# NFC.net
KiCad netlist of a schematic drawn in Altium Designer
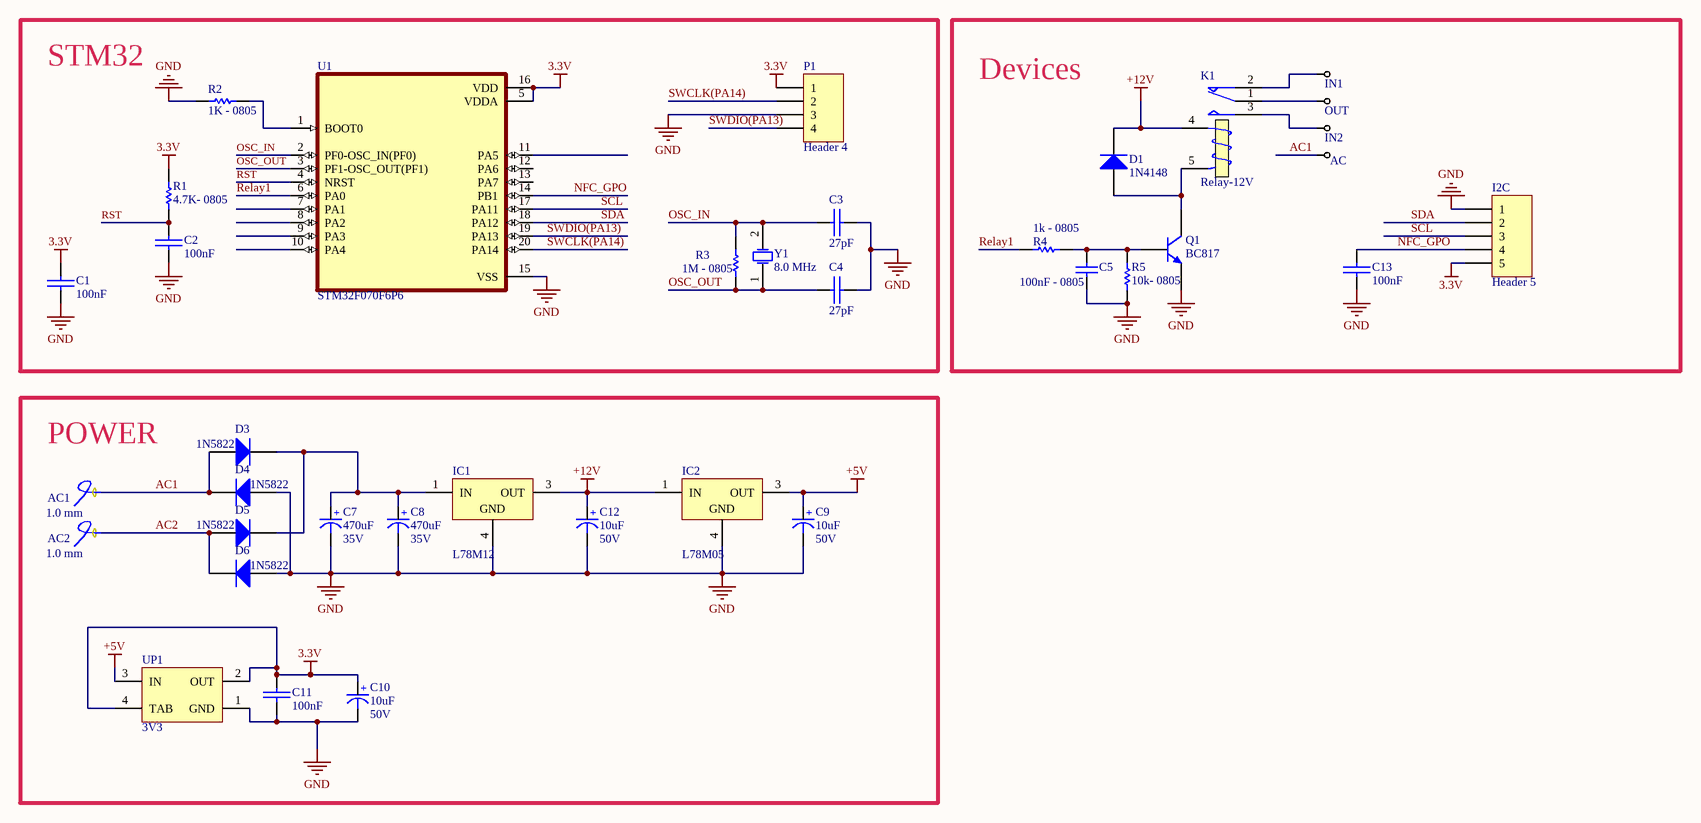
[diagram p0: NFC.SchDoc]

(export (version "E")
  (design (tool "Eeschema 10.0.6"))
  (components
    (comp (ref "AC")
      (value "Test Point")
      (footprint "Test Point")
      (libsource (lib "Altium") (part "Test Point"))
    )
    (comp (ref "AC1")
      (value "*")
      (footprint "wire 2.0 mm")
      (description "A Customize Component For Single Wire Connection")
      (fields (field (name "DIAMETER") "1.0 mm") (field (name "DESIGNER") "Saeid Jorablo"))
      (libsource (lib "My_Library") (part "Single Wire"))
    )
    (comp (ref "AC2")
      (value "*")
      (footprint "wire 2.0 mm")
      (description "A Customize Component For Single Wire Connection")
      (fields (field (name "DIAMETER") "1.0 mm") (field (name "DESIGNER") "Saeid Jorablo"))
      (libsource (lib "My_Library") (part "Single Wire"))
    )
    (comp (ref "C1")
      (value "100nF")
      (footprint "SMD_CAP_0805")
      (description "Bipolar Capacitor")
      (fields (field (name "VOLTAGE") "100V") (field (name "DESIGNER") "Saeid Jorablo"))
      (libsource (lib "My_Library") (part "Cap-Bipolar"))
    )
    (comp (ref "C2")
      (value "100nF")
      (footprint "SMD_CAP_0805")
      (description "Bipolar Capacitor")
      (fields (field (name "VOLTAGE") "100V") (field (name "DESIGNER") "Saeid Jorablo"))
      (libsource (lib "My_Library") (part "Cap-Bipolar"))
    )
    (comp (ref "C3")
      (value "27pF")
      (footprint "SMD_CAP_0805")
      (description "Bipolar Capacitor")
      (fields (field (name "VOLTAGE") "100V") (field (name "DESIGNER") "Saeid Jorablo"))
      (libsource (lib "My_Library") (part "Cap-Bipolar"))
    )
    (comp (ref "C4")
      (value "27pF")
      (footprint "SMD_CAP_0805")
      (description "Bipolar Capacitor")
      (fields (field (name "VOLTAGE") "100V") (field (name "DESIGNER") "Saeid Jorablo"))
      (libsource (lib "My_Library") (part "Cap-Bipolar"))
    )
    (comp (ref "C5")
      (value "100nF - 0805")
      (footprint "SMD_CAP_0805")
      (description "Capacitor")
      (fields (field (name "PUBLISHER") "Altium Limited"))
      (libsource (lib "Amir_Lib") (part "Cap"))
    )
    (comp (ref "C7")
      (value "470uF")
      (footprint "cap 02")
      (description "Polar Capacitor")
      (fields (field (name "VOLTAGE") "35V") (field (name "DESIGNER") "Saeid Jorablo"))
      (libsource (lib "My_Library") (part "Cap-Polar"))
    )
    (comp (ref "C8")
      (value "470uF")
      (footprint "cap 02")
      (description "Polar Capacitor")
      (fields (field (name "VOLTAGE") "35V") (field (name "DESIGNER") "Saeid Jorablo"))
      (libsource (lib "My_Library") (part "Cap-Polar"))
    )
    (comp (ref "C9")
      (value "10uF")
      (footprint "cap 01")
      (description "Polar Capacitor")
      (fields (field (name "VOLTAGE") "50V") (field (name "DESIGNER") "Saeid Jorablo"))
      (libsource (lib "My_Library") (part "Cap-Polar"))
    )
    (comp (ref "C10")
      (value "10uF")
      (footprint "cap 01")
      (description "Polar Capacitor")
      (fields (field (name "VOLTAGE") "50V") (field (name "DESIGNER") "Saeid Jorablo"))
      (libsource (lib "My_Library") (part "Cap-Polar"))
    )
    (comp (ref "C11")
      (value "100nF")
      (footprint "SMD_CAP_0805")
      (description "Bipolar Capacitor")
      (fields (field (name "VOLTAGE") "100V") (field (name "DESIGNER") "Saeid Jorablo"))
      (libsource (lib "My_Library") (part "Cap-Bipolar"))
    )
    (comp (ref "C12")
      (value "10uF")
      (footprint "cap 01")
      (description "Polar Capacitor")
      (fields (field (name "VOLTAGE") "50V") (field (name "DESIGNER") "Saeid Jorablo"))
      (libsource (lib "My_Library") (part "Cap-Polar"))
    )
    (comp (ref "C13")
      (value "100nF")
      (footprint "SMD_CAP_0805")
      (description "Bipolar Capacitor")
      (fields (field (name "VOLTAGE") "100V") (field (name "DESIGNER") "Saeid Jorablo"))
      (libsource (lib "My_Library") (part "Cap-Bipolar"))
    )
    (comp (ref "D1")
      (value "1N4148")
      (footprint "LL4148")
      (description "High Conductance Fast Diode")
      (fields (field (name "PUBLISHER") "Altium Limited"))
      (libsource (lib "My_Library") (part "Diode 1N4148"))
    )
    (comp (ref "D3")
      (value "1N5822")
      (footprint "Diode 1N4007 SMD")
      (description "High Conductance Fast Diode")
      (fields (field (name "PUBLISHER") "Altium Limited"))
      (libsource (lib "My_Library") (part "Diode 1N4148"))
    )
    (comp (ref "D4")
      (value "1N5822")
      (footprint "Diode 1N4007 SMD")
      (description "High Conductance Fast Diode")
      (fields (field (name "PUBLISHER") "Altium Limited"))
      (libsource (lib "My_Library") (part "Diode 1N4148"))
    )
    (comp (ref "D5")
      (value "1N5822")
      (footprint "Diode 1N4007 SMD")
      (description "High Conductance Fast Diode")
      (fields (field (name "PUBLISHER") "Altium Limited"))
      (libsource (lib "My_Library") (part "Diode 1N4148"))
    )
    (comp (ref "D6")
      (value "1N5822")
      (footprint "Diode 1N4007 SMD")
      (description "High Conductance Fast Diode")
      (fields (field (name "PUBLISHER") "Altium Limited"))
      (libsource (lib "My_Library") (part "Diode 1N4148"))
    )
    (comp (ref "I2C")
      (value "Header 5")
      (footprint "HDR1X5")
      (description "Header, 5-Pin")
      (fields (field (name "PUBLISHER") "Altium Limited"))
      (libsource (lib "Miscellaneous Connectors") (part "Header 5"))
    )
    (comp (ref "IC1")
      (value "L78M12")
      (footprint "TO-252")
      (description "Precision 500mA Regulator")
      (libsource (lib "My_Library") (part "L78M05"))
    )
    (comp (ref "IC2")
      (value "L78M05")
      (footprint "TO-252")
      (description "Precision 500mA Regulator")
      (libsource (lib "My_Library") (part "L78M05"))
    )
    (comp (ref "IN1")
      (value "Test Point")
      (footprint "Test Point")
      (libsource (lib "Altium") (part "Test Point"))
    )
    (comp (ref "IN2")
      (value "Test Point")
      (footprint "Test Point")
      (libsource (lib "Altium") (part "Test Point"))
    )
    (comp (ref "K1")
      (value "Relay-12V")
      (footprint "Relay 15.40x12.10x13.10")
      (description "SPDT Relay")
      (fields (field (name "DESIGNER") "Eng. Saeid Jorablo"))
      (libsource (lib "My_Library") (part "Relay"))
    )
    (comp (ref "OUT")
      (value "Test Point")
      (footprint "Test Point")
      (libsource (lib "Altium") (part "Test Point"))
    )
    (comp (ref "P1")
      (value "Header 4")
      (footprint "HDR1X4")
      (description "Header, 4-Pin")
      (fields (field (name "PUBLISHER") "Altium Limited"))
      (libsource (lib "Miscellaneous Connectors") (part "Header 4"))
    )
    (comp (ref "Q1")
      (value "BC817")
      (footprint "SOT23_N")
      (description "45 V, 500 mA NPN general-purpose transistors")
      (fields (field (name "PUBLISHER") "Abbas Basereh"))
      (libsource (lib "Altium") (part "BC817"))
    )
    (comp (ref "R1")
      (value "4.7K- 0805")
      (footprint "RES 0805 (2012X06L)")
      (description "Resistor")
      (fields (field (name "PUBLISHER") "Altium Limited"))
      (libsource (lib "Amir_Lib") (part "Res"))
    )
    (comp (ref "R2")
      (value "1K - 0805")
      (footprint "RES 0805 (2012X06L)")
      (description "Resistor")
      (fields (field (name "PUBLISHER") "Altium Limited"))
      (libsource (lib "Amir_Lib") (part "Res"))
    )
    (comp (ref "R3")
      (value "1M - 0805")
      (footprint "RES 0805 (2012X06L)")
      (description "Resistor")
      (fields (field (name "PUBLISHER") "Altium Limited"))
      (libsource (lib "Amir_Lib") (part "Res"))
    )
    (comp (ref "R4")
      (value "1k - 0805")
      (footprint "RES 0805 (2012X06L)")
      (description "Resistor")
      (fields (field (name "PUBLISHER") "Altium Limited"))
      (libsource (lib "Amir_Lib") (part "Res"))
    )
    (comp (ref "R5")
      (value "10k- 0805")
      (footprint "RES 0805 (2012X06L)")
      (description "Resistor")
      (fields (field (name "PUBLISHER") "Altium Limited"))
      (libsource (lib "Amir_Lib") (part "Res"))
    )
    (comp (ref "U1")
      (value "STM32F070F6P6")
      (footprint "SOP65P640X120-20N")
      (description "ARMÂ® CortexÂ®-M0 STM32F0 Microcontroller IC 32-Bit 48MHz 32KB _32K x 8_ FLASH 20-TSSOP")
      (fields (field (name "MF") "STMicroelectronics") (field (name "DIGI-KEY_PART_NUMBER") "497-17354-2-ND"))
      (libsource (lib "STM32F070F6P6") (part "STM32F070F6P6"))
    )
    (comp (ref "UP1")
      (value "3V3")
      (footprint "SOT223")
      (description "x.x Volt, 800mA Low-Dropout Linear Regulator, 4-pin SOT-223")
      (fields (field (name "DESIGNER") "Ali Hafizi"))
      (libsource (lib "Altium") (part "AMS1117-x.x"))
    )
    (comp (ref "Y1")
      (value "8.0 MHz")
      (footprint "Crystal SMD")
      (description "XTAL Crystal")
      (libsource (lib "My_Library") (part "XTAL"))
    )
  )
  (nets
    (net (code "1") (name "+5V") (class "Default")
      (node (ref "C9") (pin "1") (pinfunction "+_1") (pintype "passive"))
      (node (ref "IC2") (pin "3") (pinfunction "OUT_3") (pintype "power_in"))
      (node (ref "UP1") (pin "3") (pinfunction "IN_3") (pintype "power_in"))
    )
    (net (code "2") (name "+12V") (class "Default")
      (node (ref "C12") (pin "1") (pinfunction "+_1") (pintype "passive"))
      (node (ref "D1") (pin "2") (pinfunction "K_2") (pintype "passive"))
      (node (ref "IC1") (pin "3") (pinfunction "OUT_3") (pintype "power_in"))
      (node (ref "IC2") (pin "1") (pinfunction "IN_1") (pintype "power_in"))
      (node (ref "K1") (pin "4") (pinfunction "T1_4") (pintype "passive"))
    )
    (net (code "3") (name "/AC1") (class "Default")
      (node (ref "AC") (pin "1") (pinfunction "T_1") (pintype "passive"))
      (node (ref "AC1") (pin "1") (pinfunction "W_1") (pintype "passive"))
      (node (ref "D3") (pin "1") (pinfunction "A_1") (pintype "passive"))
      (node (ref "D4") (pin "2") (pinfunction "K_2") (pintype "passive"))
    )
    (net (code "4") (name "/AC2") (class "Default")
      (node (ref "AC2") (pin "1") (pinfunction "W_1") (pintype "passive"))
      (node (ref "D5") (pin "1") (pinfunction "A_1") (pintype "passive"))
      (node (ref "D6") (pin "2") (pinfunction "K_2") (pintype "passive"))
    )
    (net (code "5") (name "/NFC_GPO") (class "Default")
      (node (ref "C13") (pin "2") (pinfunction "-_2") (pintype "passive"))
      (node (ref "I2C") (pin "4") (pinfunction "4_4") (pintype "passive"))
      (node (ref "U1") (pin "14") (pinfunction "PB1_14") (pintype "bidirectional"))
    )
    (net (code "6") (name "/OSC_IN") (class "Default")
      (node (ref "C3") (pin "1") (pinfunction "+_1") (pintype "passive"))
      (node (ref "R3") (pin "2") (pinfunction "2_2") (pintype "passive"))
      (node (ref "U1") (pin "2") (pinfunction "PF0-OSC_IN(PF0)_2") (pintype "bidirectional"))
      (node (ref "Y1") (pin "2") (pinfunction "OSC2_2") (pintype "passive"))
    )
    (net (code "7") (name "/OSC_OUT") (class "Default")
      (node (ref "C4") (pin "1") (pinfunction "+_1") (pintype "passive"))
      (node (ref "R3") (pin "1") (pinfunction "1_1") (pintype "passive"))
      (node (ref "U1") (pin "3") (pinfunction "PF1-OSC_OUT(PF1)_3") (pintype "bidirectional"))
      (node (ref "Y1") (pin "1") (pinfunction "OSC1_1") (pintype "passive"))
    )
    (net (code "8") (name "/RST") (class "Default")
      (node (ref "C2") (pin "2") (pinfunction "-_2") (pintype "passive"))
      (node (ref "R1") (pin "2") (pinfunction "2_2") (pintype "passive"))
      (node (ref "U1") (pin "4") (pinfunction "NRST_4") (pintype "bidirectional"))
    )
    (net (code "9") (name "/Relay1") (class "Default")
      (node (ref "R4") (pin "2") (pinfunction "2_2") (pintype "passive"))
      (node (ref "U1") (pin "6") (pinfunction "PA0_6") (pintype "bidirectional"))
    )
    (net (code "10") (name "/SCL") (class "Default")
      (node (ref "I2C") (pin "3") (pinfunction "3_3") (pintype "passive"))
      (node (ref "U1") (pin "17") (pinfunction "PA11_17") (pintype "bidirectional"))
    )
    (net (code "11") (name "/SDA") (class "Default")
      (node (ref "I2C") (pin "2") (pinfunction "2_2") (pintype "passive"))
      (node (ref "U1") (pin "18") (pinfunction "PA12_18") (pintype "bidirectional"))
    )
    (net (code "12") (name "/SWCLK(PA14)") (class "Default")
      (node (ref "P1") (pin "2") (pinfunction "2_2") (pintype "passive"))
      (node (ref "U1") (pin "20") (pinfunction "PA14_20") (pintype "bidirectional"))
    )
    (net (code "13") (name "/SWDIO(PA13)") (class "Default")
      (node (ref "P1") (pin "4") (pinfunction "4_4") (pintype "passive"))
      (node (ref "U1") (pin "19") (pinfunction "PA13_19") (pintype "bidirectional"))
    )
    (net (code "14") (name "3.3V") (class "Default")
      (node (ref "C1") (pin "2") (pinfunction "-_2") (pintype "passive"))
      (node (ref "C10") (pin "1") (pinfunction "+_1") (pintype "passive"))
      (node (ref "C11") (pin "1") (pinfunction "+_1") (pintype "passive"))
      (node (ref "I2C") (pin "5") (pinfunction "5_5") (pintype "passive"))
      (node (ref "P1") (pin "1") (pinfunction "1_1") (pintype "passive"))
      (node (ref "R1") (pin "1") (pinfunction "1_1") (pintype "passive"))
      (node (ref "U1") (pin "16") (pinfunction "VDD_16") (pintype "power_in"))
      (node (ref "U1") (pin "5") (pinfunction "VDDA_5") (pintype "power_in"))
      (node (ref "UP1") (pin "2") (pinfunction "OUT_2") (pintype "power_in"))
      (node (ref "UP1") (pin "4") (pinfunction "TAB_4") (pintype "power_in"))
    )
    (net (code "15") (name "GND") (class "Default")
      (node (ref "C1") (pin "1") (pinfunction "+_1") (pintype "passive"))
      (node (ref "C10") (pin "2") (pinfunction "-_2") (pintype "passive"))
      (node (ref "C11") (pin "2") (pinfunction "-_2") (pintype "passive"))
      (node (ref "C12") (pin "2") (pinfunction "-_2") (pintype "passive"))
      (node (ref "C13") (pin "1") (pinfunction "+_1") (pintype "passive"))
      (node (ref "C2") (pin "1") (pinfunction "+_1") (pintype "passive"))
      (node (ref "C3") (pin "2") (pinfunction "-_2") (pintype "passive"))
      (node (ref "C4") (pin "2") (pinfunction "-_2") (pintype "passive"))
      (node (ref "C5") (pin "1") (pinfunction "1_1") (pintype "passive"))
      (node (ref "C7") (pin "2") (pinfunction "-_2") (pintype "passive"))
      (node (ref "C8") (pin "2") (pinfunction "-_2") (pintype "passive"))
      (node (ref "C9") (pin "2") (pinfunction "-_2") (pintype "passive"))
      (node (ref "D4") (pin "1") (pinfunction "A_1") (pintype "passive"))
      (node (ref "D6") (pin "1") (pinfunction "A_1") (pintype "passive"))
      (node (ref "I2C") (pin "1") (pinfunction "1_1") (pintype "passive"))
      (node (ref "IC1") (pin "4") (pinfunction "GND_4") (pintype "power_in"))
      (node (ref "IC2") (pin "4") (pinfunction "GND_4") (pintype "power_in"))
      (node (ref "P1") (pin "3") (pinfunction "3_3") (pintype "passive"))
      (node (ref "Q1") (pin "2") (pinfunction "E_2") (pintype "passive"))
      (node (ref "R2") (pin "2") (pinfunction "2_2") (pintype "passive"))
      (node (ref "R5") (pin "2") (pinfunction "2_2") (pintype "passive"))
      (node (ref "U1") (pin "15") (pinfunction "VSS_15") (pintype "power_in"))
      (node (ref "UP1") (pin "1") (pinfunction "GND_1") (pintype "power_in"))
    )
    (net (code "16") (name "Net-(C7-+)") (class "Default")
      (node (ref "C7") (pin "1") (pinfunction "+_1") (pintype "passive"))
      (node (ref "C8") (pin "1") (pinfunction "+_1") (pintype "passive"))
      (node (ref "D3") (pin "2") (pinfunction "K_2") (pintype "passive"))
      (node (ref "D5") (pin "2") (pinfunction "K_2") (pintype "passive"))
      (node (ref "IC1") (pin "1") (pinfunction "IN_1") (pintype "power_in"))
    )
    (net (code "17") (name "Net-(D1-A)") (class "Default")
      (node (ref "D1") (pin "1") (pinfunction "A_1") (pintype "passive"))
      (node (ref "K1") (pin "5") (pinfunction "T2_5") (pintype "passive"))
      (node (ref "Q1") (pin "3") (pinfunction "C_3") (pintype "passive"))
    )
    (net (code "18") (name "Net-(IN1-T)") (class "Default")
      (node (ref "IN1") (pin "1") (pinfunction "T_1") (pintype "passive"))
      (node (ref "K1") (pin "2") (pinfunction "NC_2") (pintype "passive"))
    )
    (net (code "19") (name "Net-(IN2-T)") (class "Default")
      (node (ref "IN2") (pin "1") (pinfunction "T_1") (pintype "passive"))
      (node (ref "K1") (pin "3") (pinfunction "NO_3") (pintype "passive"))
    )
    (net (code "20") (name "Net-(K1-COM)") (class "Default")
      (node (ref "K1") (pin "1") (pinfunction "COM_1") (pintype "passive"))
      (node (ref "OUT") (pin "1") (pinfunction "T_1") (pintype "passive"))
    )
    (net (code "21") (name "Net-(Q1-B)") (class "Default")
      (node (ref "C5") (pin "2") (pinfunction "2_2") (pintype "passive"))
      (node (ref "Q1") (pin "1") (pinfunction "B_1") (pintype "passive"))
      (node (ref "R4") (pin "1") (pinfunction "1_1") (pintype "passive"))
      (node (ref "R5") (pin "1") (pinfunction "1_1") (pintype "passive"))
    )
    (net (code "22") (name "Net-(U1-BOOT0)") (class "Default")
      (node (ref "R2") (pin "1") (pinfunction "1_1") (pintype "passive"))
      (node (ref "U1") (pin "1") (pinfunction "BOOT0_1") (pintype "input"))
    )
    (net (code "23") (name "unconnected-(U1-PA1-Pad7)") (class "Default")
      (node (ref "U1") (pin "7") (pinfunction "PA1_7") (pintype "bidirectional"))
    )
    (net (code "24") (name "unconnected-(U1-PA2-Pad8)") (class "Default")
      (node (ref "U1") (pin "8") (pinfunction "PA2_8") (pintype "bidirectional"))
    )
    (net (code "25") (name "unconnected-(U1-PA3-Pad9)") (class "Default")
      (node (ref "U1") (pin "9") (pinfunction "PA3_9") (pintype "bidirectional"))
    )
    (net (code "26") (name "unconnected-(U1-PA4-Pad10)") (class "Default")
      (node (ref "U1") (pin "10") (pinfunction "PA4_10") (pintype "bidirectional"))
    )
    (net (code "27") (name "unconnected-(U1-PA5-Pad11)") (class "Default")
      (node (ref "U1") (pin "11") (pinfunction "PA5_11") (pintype "bidirectional"))
    )
    (net (code "28") (name "unconnected-(U1-PA6-Pad12)") (class "Default")
      (node (ref "U1") (pin "12") (pinfunction "PA6_12") (pintype "bidirectional"))
    )
    (net (code "29") (name "unconnected-(U1-PA7-Pad13)") (class "Default")
      (node (ref "U1") (pin "13") (pinfunction "PA7_13") (pintype "bidirectional"))
    )
  )
)
